# stm.net
KiCad netlist of a schematic drawn in Altium Designer
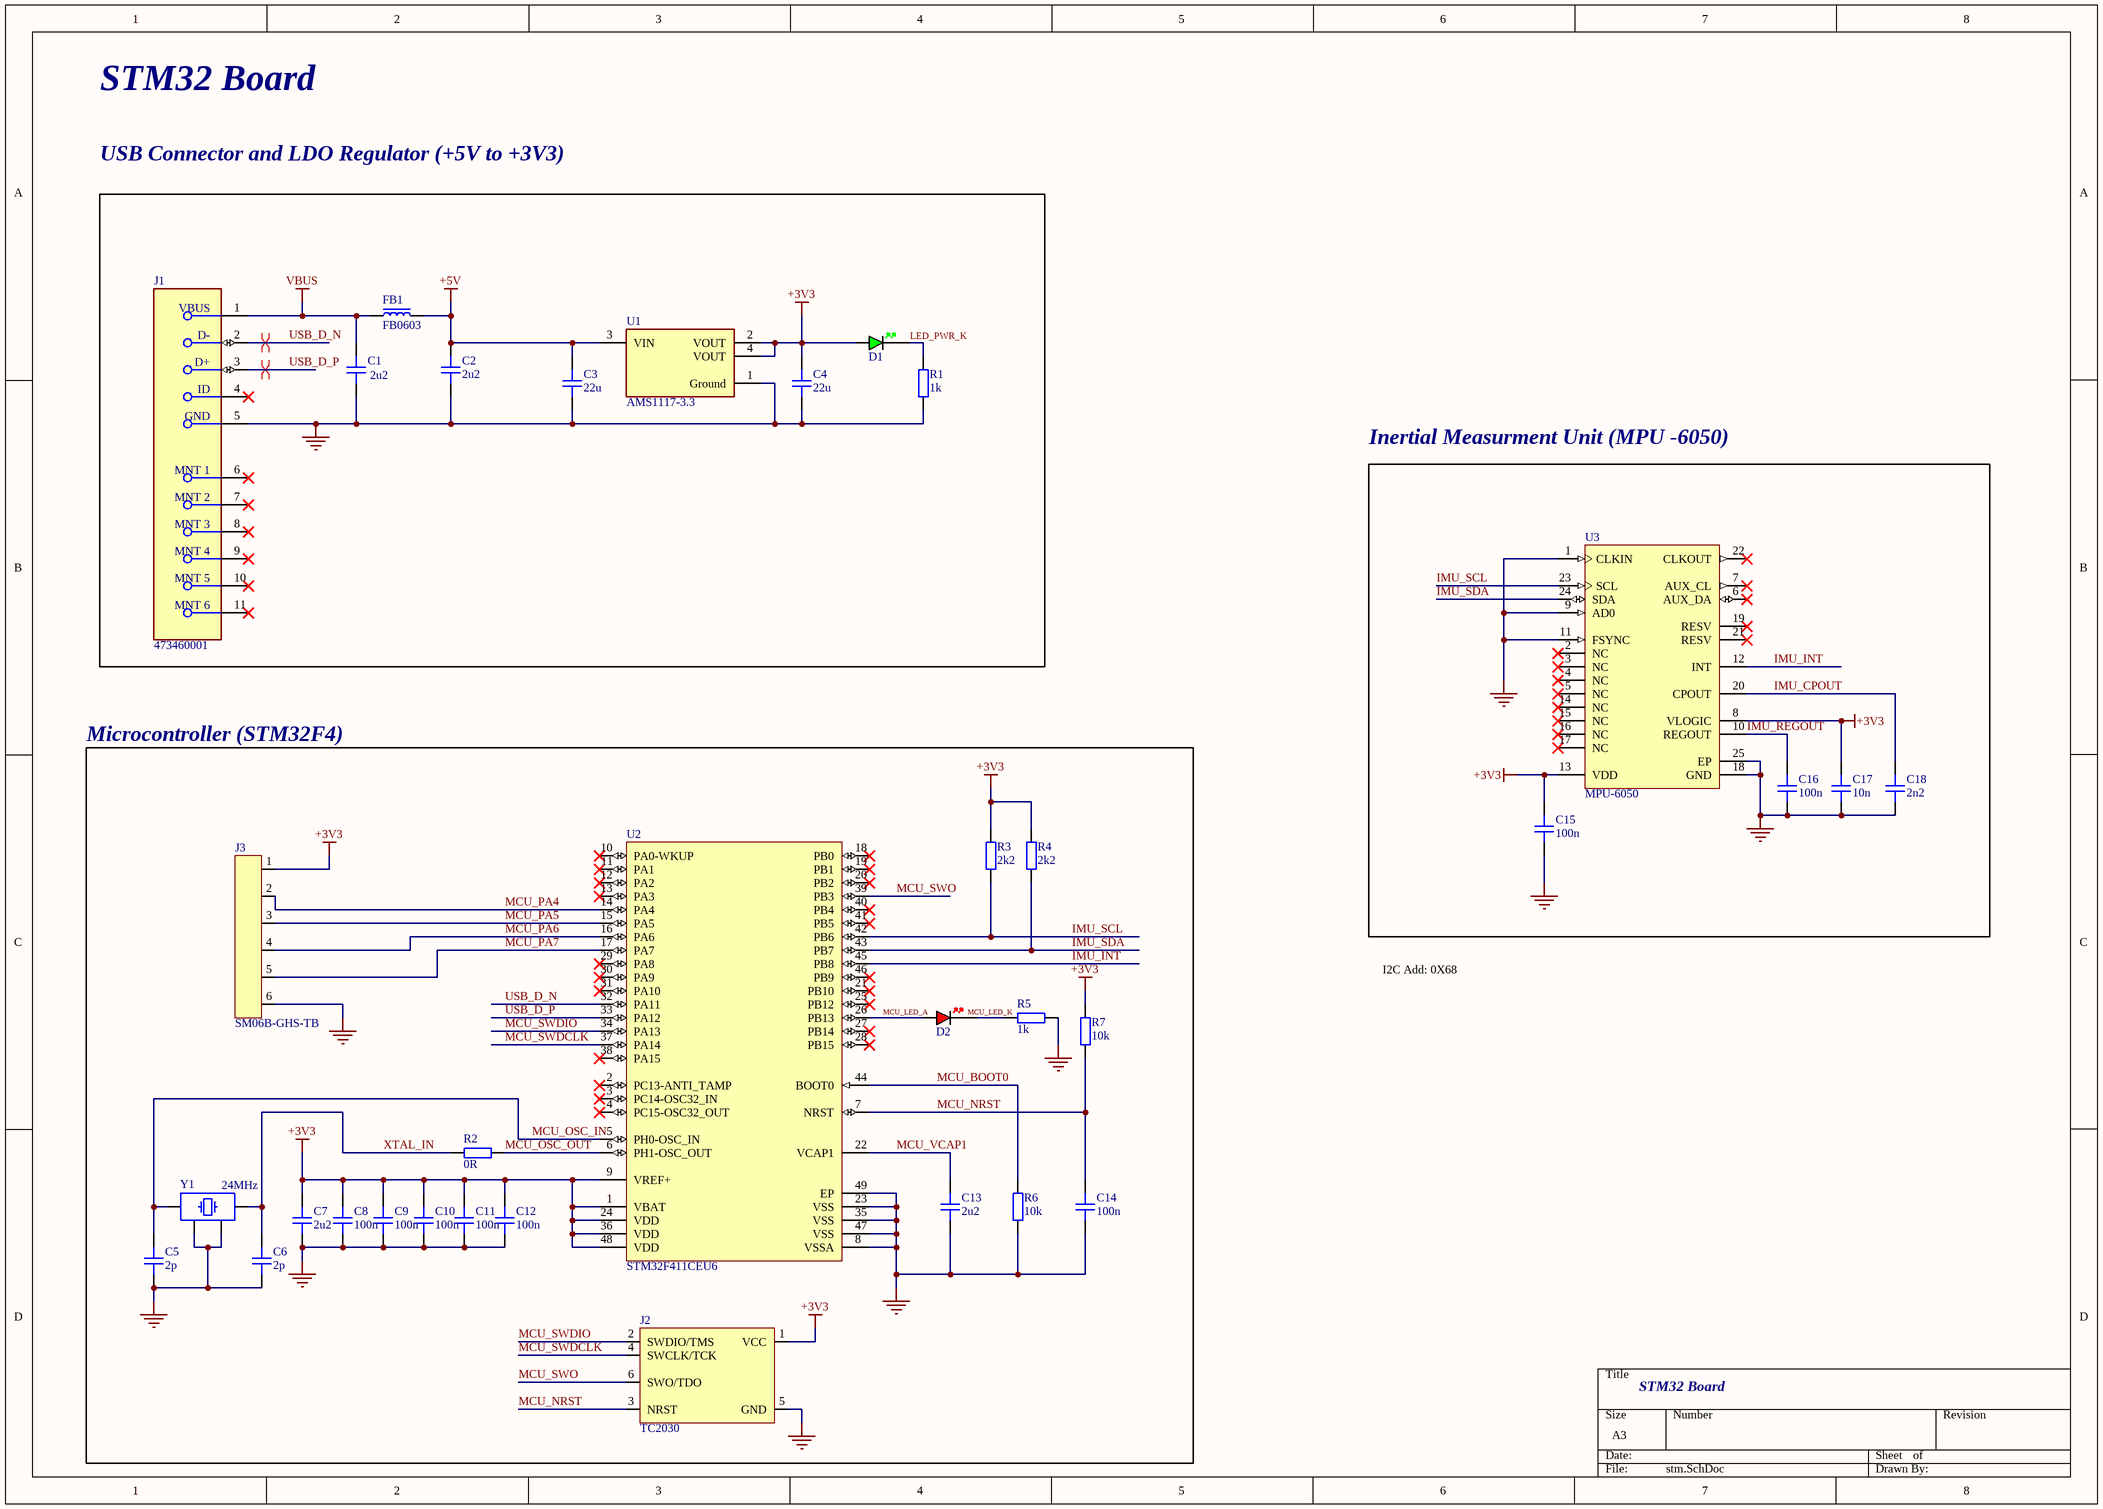
[diagram p0: stm.SchDoc]

(export (version "E")
  (design (tool "Eeschema 10.0.6"))
  (components
    (comp (ref "C1")
      (value "2u2")
      (footprint "CAP_0603")
      (description "Capacitor SMD 0603")
      (libsource (lib "Schematic-Lib-PhilsLab") (part "CAP_0603"))
    )
    (comp (ref "C2")
      (value "2u2")
      (footprint "CAP_0603")
      (description "Capacitor SMD 0603")
      (libsource (lib "Schematic-Lib-PhilsLab") (part "CAP_0603"))
    )
    (comp (ref "C3")
      (value "22u")
      (footprint "CAP_0805")
      (description "Capacitor SMD 0805")
      (libsource (lib "Schematic-Lib-PhilsLab") (part "CAP_0805"))
    )
    (comp (ref "C4")
      (value "22u")
      (footprint "CAP_0805")
      (description "Capacitor SMD 0805")
      (libsource (lib "Schematic-Lib-PhilsLab") (part "CAP_0805"))
    )
    (comp (ref "C5")
      (value "2p")
      (footprint "CAP_0402")
      (description "Capacitor SMD 0402")
      (libsource (lib "Schematic-Lib-PhilsLab") (part "CAP_0402"))
    )
    (comp (ref "C6")
      (value "2p")
      (footprint "CAP_0402")
      (description "Capacitor SMD 0402")
      (libsource (lib "Schematic-Lib-PhilsLab") (part "CAP_0402"))
    )
    (comp (ref "C7")
      (value "2u2")
      (footprint "CAP_0603")
      (description "Capacitor SMD 0603")
      (libsource (lib "Schematic-Lib-PhilsLab") (part "CAP_0603"))
    )
    (comp (ref "C8")
      (value "100n")
      (footprint "CAP_0402")
      (description "Capacitor SMD 0402")
      (libsource (lib "Schematic-Lib-PhilsLab") (part "CAP_0402"))
    )
    (comp (ref "C9")
      (value "100n")
      (footprint "CAP_0402")
      (description "Capacitor SMD 0402")
      (libsource (lib "Schematic-Lib-PhilsLab") (part "CAP_0402"))
    )
    (comp (ref "C10")
      (value "100n")
      (footprint "CAP_0402")
      (description "Capacitor SMD 0402")
      (libsource (lib "Schematic-Lib-PhilsLab") (part "CAP_0402"))
    )
    (comp (ref "C11")
      (value "100n")
      (footprint "CAP_0402")
      (description "Capacitor SMD 0402")
      (libsource (lib "Schematic-Lib-PhilsLab") (part "CAP_0402"))
    )
    (comp (ref "C12")
      (value "100n")
      (footprint "CAP_0402")
      (description "Capacitor SMD 0402")
      (libsource (lib "Schematic-Lib-PhilsLab") (part "CAP_0402"))
    )
    (comp (ref "C13")
      (value "2u2")
      (footprint "CAP_0603")
      (description "Capacitor SMD 0603")
      (libsource (lib "Schematic-Lib-PhilsLab") (part "CAP_0603"))
    )
    (comp (ref "C14")
      (value "100n")
      (footprint "CAP_0402")
      (description "Capacitor SMD 0402")
      (libsource (lib "Schematic-Lib-PhilsLab") (part "CAP_0402"))
    )
    (comp (ref "C15")
      (value "100n")
      (footprint "CAP_0402")
      (description "Capacitor SMD 0402")
      (libsource (lib "Schematic-Lib-PhilsLab") (part "CAP_0402"))
    )
    (comp (ref "C16")
      (value "100n")
      (footprint "CAP_0402")
      (description "Capacitor SMD 0402")
      (libsource (lib "Schematic-Lib-PhilsLab") (part "CAP_0402"))
    )
    (comp (ref "C17")
      (value "10n")
      (footprint "CAP_0402")
      (description "Capacitor SMD 0402")
      (libsource (lib "Schematic-Lib-PhilsLab") (part "CAP_0402"))
    )
    (comp (ref "C18")
      (value "2n2")
      (footprint "CAP_0402")
      (description "Capacitor SMD 0402")
      (libsource (lib "Schematic-Lib-PhilsLab") (part "CAP_0402"))
    )
    (comp (ref "D1")
      (value "GREEN")
      (footprint "LED_0402_GREEN")
      (description "LED 0402 GREEN SMD")
      (libsource (lib "Schematic-Lib-PhilsLab") (part "LED_0402_GREEN"))
    )
    (comp (ref "D2")
      (value "RED")
      (footprint "LED_0402_RED")
      (description "LED 0402 RED SMD")
      (libsource (lib "Schematic-Lib-PhilsLab") (part "LED_0402_RED"))
    )
    (comp (ref "FB1")
      (value "FB0603")
      (footprint "FB_0603")
      (description "Ferrite Bead SMD 0603")
      (libsource (lib "Schematic-Lib-PhilsLab") (part "FB_0603"))
    )
    (comp (ref "J1")
      (value "473460001")
      (footprint "FP-473460001-MFG")
      (description "CONN RCPT USB2.0 MICRO B SMD R/A")
      (fields
        (field (name "OCTOPART") "https://octopart.com/47346-0001-molex-7164928")
        (field (name "MANUFACTURER") "Molex")
      )
      (libsource (lib "Altium Content Vault") (part "53ae1f1d9b557310b43ca686e5bb76a"))
    )
    (comp (ref "J2")
      (value "TC2030")
      (footprint "TC2030-FP")
      (description "Tag-Connect No-Solder SWD Debug Connector DO NOT PLACE")
      (fields (field (name "MANUFACTURER") "Tag-Connect"))
      (libsource (lib "Schematic-Lib-PhilsLab") (part "TC2030"))
    )
    (comp (ref "J3")
      (value "SM06B-GHS-TB")
      (footprint "SM06B-GHS-TB")
      (description "Header Connector 6 Position 1.25MM Pitch SMD Horizontal JST GH")
      (fields (field (name "MANUFACTURER") "JST"))
      (libsource (lib "Schematic-Lib-PhilsLab") (part "SM06B-GHS-TB"))
    )
    (comp (ref "R1")
      (value "1k")
      (footprint "RES_0402")
      (description "Resistor SMD 0402")
      (libsource (lib "Schematic-Lib-PhilsLab") (part "RES_0402"))
    )
    (comp (ref "R2")
      (value "0R")
      (footprint "RES_0402")
      (description "Resistor SMD 0402")
      (libsource (lib "Schematic-Lib-PhilsLab") (part "RES_0402"))
    )
    (comp (ref "R3")
      (value "2k2")
      (footprint "RES_0402")
      (description "Resistor SMD 0402")
      (libsource (lib "Schematic-Lib-PhilsLab") (part "RES_0402"))
    )
    (comp (ref "R4")
      (value "2k2")
      (footprint "RES_0402")
      (description "Resistor SMD 0402")
      (libsource (lib "Schematic-Lib-PhilsLab") (part "RES_0402"))
    )
    (comp (ref "R5")
      (value "1k")
      (footprint "RES_0402")
      (description "Resistor SMD 0402")
      (libsource (lib "Schematic-Lib-PhilsLab") (part "RES_0402"))
    )
    (comp (ref "R6")
      (value "10k")
      (footprint "RES_0402")
      (description "Resistor SMD 0402")
      (libsource (lib "Schematic-Lib-PhilsLab") (part "RES_0402"))
    )
    (comp (ref "R7")
      (value "10k")
      (footprint "RES_0402")
      (description "Resistor SMD 0402")
      (libsource (lib "Schematic-Lib-PhilsLab") (part "RES_0402"))
    )
    (comp (ref "U1")
      (value "AMS1117-3.3")
      (footprint "FP-AMS1117-IPC_C")
      (description "LDO Voltage Regulators 1A, 3.3V")
      (fields
        (field (name "OCTOPART") "https://octopart.com/ams1117-3.3-advanced+monolithic+systems-25899300")
        (field (name "MANUFACTURER") "Advanced Monolithic Systems")
      )
      (libsource (lib "Altium Content Vault") (part "8bdbb5f8e77002000e30dd2845d0354"))
    )
    (comp (ref "U2")
      (value "STM32F411CEU6")
      (footprint "STM-UFQFPN48_L")
      (libsource (lib "Altium Content Vault") (part "MC-ARM-STM32F411-UFQFPN48"))
    )
    (comp (ref "U3")
      (value "MPU-6050")
      (footprint "IS-QFN-24_V")
      (fields (field (name "MANUFACTURER") "InvenSense"))
      (libsource (lib "Altium Content Vault") (part "IS-MPU-6050-QFN-24"))
    )
    (comp (ref "Y1")
      (value "24MHz")
      (footprint "XTAL_3225")
      (description "Crystal SMD 24MHz 10PPM 7pF 3225")
      (fields
        (field (name "MANUFACTURER") "Epson")
        (field (name "MANUFACTURER PART NUMBER") "TSX-3225 24.0000MF15X-AC")
      )
      (libsource (lib "Schematic-Lib-PhilsLab") (part "TSX-3225_24.0000MF15X-AC"))
    )
  )
  (nets
    (net (code "1") (name "+3V3") (class "Default")
      (node (ref "C10") (pin "2") (pinfunction "2_2") (pintype "passive"))
      (node (ref "C11") (pin "2") (pinfunction "2_2") (pintype "passive"))
      (node (ref "C12") (pin "2") (pinfunction "2_2") (pintype "passive"))
      (node (ref "C15") (pin "2") (pinfunction "2_2") (pintype "passive"))
      (node (ref "C17") (pin "2") (pinfunction "2_2") (pintype "passive"))
      (node (ref "C4") (pin "2") (pinfunction "2_2") (pintype "passive"))
      (node (ref "C7") (pin "2") (pinfunction "2_2") (pintype "passive"))
      (node (ref "C8") (pin "2") (pinfunction "2_2") (pintype "passive"))
      (node (ref "C9") (pin "2") (pinfunction "2_2") (pintype "passive"))
      (node (ref "D1") (pin "A") (pinfunction "A_A") (pintype "passive"))
      (node (ref "J2") (pin "1") (pinfunction "VCC_1") (pintype "passive"))
      (node (ref "J3") (pin "1") (pinfunction "1_1") (pintype "passive"))
      (node (ref "R3") (pin "2") (pinfunction "2_2") (pintype "passive"))
      (node (ref "R4") (pin "2") (pinfunction "2_2") (pintype "passive"))
      (node (ref "R7") (pin "2") (pinfunction "2_2") (pintype "passive"))
      (node (ref "U1") (pin "2") (pinfunction "VOUT_2") (pintype "passive"))
      (node (ref "U1") (pin "4") (pinfunction "VOUT_4") (pintype "passive"))
      (node (ref "U2") (pin "1") (pinfunction "VBAT_1") (pintype "power_in"))
      (node (ref "U2") (pin "24") (pinfunction "VDD_24") (pintype "power_in"))
      (node (ref "U2") (pin "36") (pinfunction "VDD_36") (pintype "power_in"))
      (node (ref "U2") (pin "48") (pinfunction "VDD_48") (pintype "power_in"))
      (node (ref "U2") (pin "9") (pinfunction "VREF+_9") (pintype "power_in"))
      (node (ref "U3") (pin "13") (pinfunction "VDD_13") (pintype "power_in"))
      (node (ref "U3") (pin "8") (pinfunction "VLOGIC_8") (pintype "power_in"))
    )
    (net (code "2") (name "+5V") (class "Default")
      (node (ref "C2") (pin "2") (pinfunction "2_2") (pintype "passive"))
      (node (ref "C3") (pin "2") (pinfunction "2_2") (pintype "passive"))
      (node (ref "FB1") (pin "2") (pinfunction "2_2") (pintype "passive"))
      (node (ref "U1") (pin "3") (pinfunction "VIN_3") (pintype "power_in"))
    )
    (net (code "3") (name "/IMU_CPOUT") (class "Default")
      (node (ref "C18") (pin "2") (pinfunction "2_2") (pintype "passive"))
      (node (ref "U3") (pin "20") (pinfunction "CPOUT_20") (pintype "passive"))
    )
    (net (code "4") (name "/IMU_INT") (class "Default")
      (node (ref "U2") (pin "45") (pinfunction "PB8_45") (pintype "bidirectional"))
      (node (ref "U3") (pin "12") (pinfunction "INT_12") (pintype "open_collector"))
    )
    (net (code "5") (name "/IMU_REGOUT") (class "Default")
      (node (ref "C16") (pin "2") (pinfunction "2_2") (pintype "passive"))
      (node (ref "U3") (pin "10") (pinfunction "REGOUT_10") (pintype "passive"))
    )
    (net (code "6") (name "/IMU_SCL") (class "Default")
      (node (ref "R3") (pin "1") (pinfunction "1_1") (pintype "passive"))
      (node (ref "U2") (pin "42") (pinfunction "PB6_42") (pintype "bidirectional"))
      (node (ref "U3") (pin "23") (pinfunction "SCL_23") (pintype "input"))
    )
    (net (code "7") (name "/IMU_SDA") (class "Default")
      (node (ref "R4") (pin "1") (pinfunction "1_1") (pintype "passive"))
      (node (ref "U2") (pin "43") (pinfunction "PB7_43") (pintype "bidirectional"))
      (node (ref "U3") (pin "24") (pinfunction "SDA_24") (pintype "bidirectional"))
    )
    (net (code "8") (name "/LED_PWR_K") (class "Default")
      (node (ref "D1") (pin "K") (pinfunction "K_K") (pintype "passive"))
      (node (ref "R1") (pin "1") (pinfunction "1_1") (pintype "passive"))
    )
    (net (code "9") (name "/MCU_BOOT0") (class "Default")
      (node (ref "R6") (pin "2") (pinfunction "2_2") (pintype "passive"))
      (node (ref "U2") (pin "44") (pinfunction "BOOT0_44") (pintype "input"))
    )
    (net (code "10") (name "/MCU_LED_A") (class "Default")
      (node (ref "D2") (pin "A") (pinfunction "A_A") (pintype "passive"))
      (node (ref "U2") (pin "26") (pinfunction "PB13_26") (pintype "bidirectional"))
    )
    (net (code "11") (name "/MCU_LED_K") (class "Default")
      (node (ref "D2") (pin "K") (pinfunction "K_K") (pintype "passive"))
      (node (ref "R5") (pin "2") (pinfunction "2_2") (pintype "passive"))
    )
    (net (code "12") (name "/MCU_NRST") (class "Default")
      (node (ref "C14") (pin "2") (pinfunction "2_2") (pintype "passive"))
      (node (ref "J2") (pin "3") (pinfunction "NRST_3") (pintype "passive"))
      (node (ref "R7") (pin "1") (pinfunction "1_1") (pintype "passive"))
      (node (ref "U2") (pin "7") (pinfunction "NRST_7") (pintype "bidirectional"))
    )
    (net (code "13") (name "/MCU_OSC_IN") (class "Default")
      (node (ref "C5") (pin "2") (pinfunction "2_2") (pintype "passive"))
      (node (ref "U2") (pin "5") (pinfunction "PH0-OSC_IN_5") (pintype "bidirectional"))
      (node (ref "Y1") (pin "1") (pinfunction "1_1") (pintype "passive"))
    )
    (net (code "14") (name "/MCU_OSC_OUT") (class "Default")
      (node (ref "R2") (pin "1") (pinfunction "1_1") (pintype "passive"))
      (node (ref "U2") (pin "6") (pinfunction "PH1-OSC_OUT_6") (pintype "bidirectional"))
    )
    (net (code "15") (name "/MCU_PA4") (class "Default")
      (node (ref "J3") (pin "2") (pinfunction "2_2") (pintype "passive"))
      (node (ref "U2") (pin "14") (pinfunction "PA4_14") (pintype "bidirectional"))
    )
    (net (code "16") (name "/MCU_PA5") (class "Default")
      (node (ref "J3") (pin "3") (pinfunction "3_3") (pintype "passive"))
      (node (ref "U2") (pin "15") (pinfunction "PA5_15") (pintype "bidirectional"))
    )
    (net (code "17") (name "/MCU_PA6") (class "Default")
      (node (ref "J3") (pin "4") (pinfunction "4_4") (pintype "passive"))
      (node (ref "U2") (pin "16") (pinfunction "PA6_16") (pintype "bidirectional"))
    )
    (net (code "18") (name "/MCU_PA7") (class "Default")
      (node (ref "J3") (pin "5") (pinfunction "5_5") (pintype "passive"))
      (node (ref "U2") (pin "17") (pinfunction "PA7_17") (pintype "bidirectional"))
    )
    (net (code "19") (name "/MCU_SWDCLK") (class "Default")
      (node (ref "J2") (pin "4") (pinfunction "SWCLK/TCK_4") (pintype "passive"))
      (node (ref "U2") (pin "37") (pinfunction "PA14_37") (pintype "bidirectional"))
    )
    (net (code "20") (name "/MCU_SWDIO") (class "Default")
      (node (ref "J2") (pin "2") (pinfunction "SWDIO/TMS_2") (pintype "passive"))
      (node (ref "U2") (pin "34") (pinfunction "PA13_34") (pintype "bidirectional"))
    )
    (net (code "21") (name "/MCU_SWO") (class "Default")
      (node (ref "J2") (pin "6") (pinfunction "SWO/TDO_6") (pintype "passive"))
      (node (ref "U2") (pin "39") (pinfunction "PB3_39") (pintype "bidirectional"))
    )
    (net (code "22") (name "/MCU_VCAP1") (class "Default")
      (node (ref "C13") (pin "2") (pinfunction "2_2") (pintype "passive"))
      (node (ref "U2") (pin "22") (pinfunction "VCAP1_22") (pintype "passive"))
    )
    (net (code "23") (name "/USB_D_N") (class "Default")
      (node (ref "J1") (pin "2") (pinfunction "D-_2") (pintype "bidirectional"))
      (node (ref "U2") (pin "32") (pinfunction "PA11_32") (pintype "bidirectional"))
    )
    (net (code "24") (name "/USB_D_P") (class "Default")
      (node (ref "J1") (pin "3") (pinfunction "D+_3") (pintype "bidirectional"))
      (node (ref "U2") (pin "33") (pinfunction "PA12_33") (pintype "bidirectional"))
    )
    (net (code "25") (name "/XTAL_IN") (class "Default")
      (node (ref "C6") (pin "2") (pinfunction "2_2") (pintype "passive"))
      (node (ref "R2") (pin "2") (pinfunction "2_2") (pintype "passive"))
      (node (ref "Y1") (pin "3") (pinfunction "3_3") (pintype "passive"))
    )
    (net (code "26") (name "GND") (class "Default")
      (node (ref "C1") (pin "1") (pinfunction "1_1") (pintype "passive"))
      (node (ref "C10") (pin "1") (pinfunction "1_1") (pintype "passive"))
      (node (ref "C11") (pin "1") (pinfunction "1_1") (pintype "passive"))
      (node (ref "C12") (pin "1") (pinfunction "1_1") (pintype "passive"))
      (node (ref "C13") (pin "1") (pinfunction "1_1") (pintype "passive"))
      (node (ref "C14") (pin "1") (pinfunction "1_1") (pintype "passive"))
      (node (ref "C15") (pin "1") (pinfunction "1_1") (pintype "passive"))
      (node (ref "C16") (pin "1") (pinfunction "1_1") (pintype "passive"))
      (node (ref "C17") (pin "1") (pinfunction "1_1") (pintype "passive"))
      (node (ref "C18") (pin "1") (pinfunction "1_1") (pintype "passive"))
      (node (ref "C2") (pin "1") (pinfunction "1_1") (pintype "passive"))
      (node (ref "C3") (pin "1") (pinfunction "1_1") (pintype "passive"))
      (node (ref "C4") (pin "1") (pinfunction "1_1") (pintype "passive"))
      (node (ref "C5") (pin "1") (pinfunction "1_1") (pintype "passive"))
      (node (ref "C6") (pin "1") (pinfunction "1_1") (pintype "passive"))
      (node (ref "C7") (pin "1") (pinfunction "1_1") (pintype "passive"))
      (node (ref "C8") (pin "1") (pinfunction "1_1") (pintype "passive"))
      (node (ref "C9") (pin "1") (pinfunction "1_1") (pintype "passive"))
      (node (ref "J1") (pin "5") (pinfunction "GND_5") (pintype "power_in"))
      (node (ref "J2") (pin "5") (pinfunction "GND_5") (pintype "passive"))
      (node (ref "J3") (pin "6") (pinfunction "6_6") (pintype "passive"))
      (node (ref "R1") (pin "2") (pinfunction "2_2") (pintype "passive"))
      (node (ref "R5") (pin "1") (pinfunction "1_1") (pintype "passive"))
      (node (ref "R6") (pin "1") (pinfunction "1_1") (pintype "passive"))
      (node (ref "U1") (pin "1") (pinfunction "Ground_1") (pintype "power_in"))
      (node (ref "U2") (pin "23") (pinfunction "VSS_23") (pintype "power_in"))
      (node (ref "U2") (pin "35") (pinfunction "VSS_35") (pintype "power_in"))
      (node (ref "U2") (pin "47") (pinfunction "VSS_47") (pintype "power_in"))
      (node (ref "U2") (pin "49") (pinfunction "EP_49") (pintype "power_in"))
      (node (ref "U2") (pin "8") (pinfunction "VSSA_8") (pintype "power_in"))
      (node (ref "U3") (pin "1") (pinfunction "CLKIN_1") (pintype "input"))
      (node (ref "U3") (pin "11") (pinfunction "FSYNC_11") (pintype "input"))
      (node (ref "U3") (pin "18") (pinfunction "GND_18") (pintype "power_in"))
      (node (ref "U3") (pin "25") (pinfunction "EP_25") (pintype "power_in"))
      (node (ref "U3") (pin "9") (pinfunction "AD0_9") (pintype "input"))
      (node (ref "Y1") (pin "2") (pinfunction "2_2") (pintype "passive"))
      (node (ref "Y1") (pin "4") (pinfunction "4_4") (pintype "passive"))
    )
    (net (code "27") (name "VBUS") (class "Default")
      (node (ref "C1") (pin "2") (pinfunction "2_2") (pintype "passive"))
      (node (ref "FB1") (pin "1") (pinfunction "1_1") (pintype "passive"))
      (node (ref "J1") (pin "1") (pinfunction "VBUS_1") (pintype "power_in"))
    )
    (net (code "28") (name "unconnected-(J1-ID-Pad4)") (class "Default")
      (node (ref "J1") (pin "4") (pinfunction "ID_4") (pintype "passive+no_connect"))
    )
    (net (code "29") (name "unconnected-(J1-MNT_1-Pad6)") (class "Default")
      (node (ref "J1") (pin "6") (pinfunction "MNT_1_6") (pintype "passive+no_connect"))
    )
    (net (code "30") (name "unconnected-(J1-MNT_2-Pad7)") (class "Default")
      (node (ref "J1") (pin "7") (pinfunction "MNT_2_7") (pintype "passive+no_connect"))
    )
    (net (code "31") (name "unconnected-(J1-MNT_3-Pad8)") (class "Default")
      (node (ref "J1") (pin "8") (pinfunction "MNT_3_8") (pintype "passive+no_connect"))
    )
    (net (code "32") (name "unconnected-(J1-MNT_4-Pad9)") (class "Default")
      (node (ref "J1") (pin "9") (pinfunction "MNT_4_9") (pintype "passive+no_connect"))
    )
    (net (code "33") (name "unconnected-(J1-MNT_5-Pad10)") (class "Default")
      (node (ref "J1") (pin "10") (pinfunction "MNT_5_10") (pintype "passive+no_connect"))
    )
    (net (code "34") (name "unconnected-(J1-MNT_6-Pad11)") (class "Default")
      (node (ref "J1") (pin "11") (pinfunction "MNT_6_11") (pintype "passive+no_connect"))
    )
    (net (code "35") (name "unconnected-(U2-PA0-WKUP-Pad10)") (class "Default")
      (node (ref "U2") (pin "10") (pinfunction "PA0-WKUP_10") (pintype "bidirectional+no_connect"))
    )
    (net (code "36") (name "unconnected-(U2-PA1-Pad11)") (class "Default")
      (node (ref "U2") (pin "11") (pinfunction "PA1_11") (pintype "bidirectional+no_connect"))
    )
    (net (code "37") (name "unconnected-(U2-PA2-Pad12)") (class "Default")
      (node (ref "U2") (pin "12") (pinfunction "PA2_12") (pintype "bidirectional+no_connect"))
    )
    (net (code "38") (name "unconnected-(U2-PA3-Pad13)") (class "Default")
      (node (ref "U2") (pin "13") (pinfunction "PA3_13") (pintype "bidirectional+no_connect"))
    )
    (net (code "39") (name "unconnected-(U2-PA8-Pad29)") (class "Default")
      (node (ref "U2") (pin "29") (pinfunction "PA8_29") (pintype "bidirectional+no_connect"))
    )
    (net (code "40") (name "unconnected-(U2-PA9-Pad30)") (class "Default")
      (node (ref "U2") (pin "30") (pinfunction "PA9_30") (pintype "bidirectional+no_connect"))
    )
    (net (code "41") (name "unconnected-(U2-PA10-Pad31)") (class "Default")
      (node (ref "U2") (pin "31") (pinfunction "PA10_31") (pintype "bidirectional+no_connect"))
    )
    (net (code "42") (name "unconnected-(U2-PA15-Pad38)") (class "Default")
      (node (ref "U2") (pin "38") (pinfunction "PA15_38") (pintype "bidirectional+no_connect"))
    )
    (net (code "43") (name "unconnected-(U2-PB0-Pad18)") (class "Default")
      (node (ref "U2") (pin "18") (pinfunction "PB0_18") (pintype "bidirectional+no_connect"))
    )
    (net (code "44") (name "unconnected-(U2-PB1-Pad19)") (class "Default")
      (node (ref "U2") (pin "19") (pinfunction "PB1_19") (pintype "bidirectional+no_connect"))
    )
    (net (code "45") (name "unconnected-(U2-PB2-Pad20)") (class "Default")
      (node (ref "U2") (pin "20") (pinfunction "PB2_20") (pintype "bidirectional+no_connect"))
    )
    (net (code "46") (name "unconnected-(U2-PB4-Pad40)") (class "Default")
      (node (ref "U2") (pin "40") (pinfunction "PB4_40") (pintype "bidirectional+no_connect"))
    )
    (net (code "47") (name "unconnected-(U2-PB5-Pad41)") (class "Default")
      (node (ref "U2") (pin "41") (pinfunction "PB5_41") (pintype "bidirectional+no_connect"))
    )
    (net (code "48") (name "unconnected-(U2-PB9-Pad46)") (class "Default")
      (node (ref "U2") (pin "46") (pinfunction "PB9_46") (pintype "bidirectional+no_connect"))
    )
    (net (code "49") (name "unconnected-(U2-PB10-Pad21)") (class "Default")
      (node (ref "U2") (pin "21") (pinfunction "PB10_21") (pintype "bidirectional+no_connect"))
    )
    (net (code "50") (name "unconnected-(U2-PB12-Pad25)") (class "Default")
      (node (ref "U2") (pin "25") (pinfunction "PB12_25") (pintype "bidirectional+no_connect"))
    )
    (net (code "51") (name "unconnected-(U2-PB14-Pad27)") (class "Default")
      (node (ref "U2") (pin "27") (pinfunction "PB14_27") (pintype "bidirectional+no_connect"))
    )
    (net (code "52") (name "unconnected-(U2-PB15-Pad28)") (class "Default")
      (node (ref "U2") (pin "28") (pinfunction "PB15_28") (pintype "bidirectional+no_connect"))
    )
    (net (code "53") (name "unconnected-(U2-PC13-ANTI_TAMP-Pad2)") (class "Default")
      (node (ref "U2") (pin "2") (pinfunction "PC13-ANTI_TAMP_2") (pintype "bidirectional+no_connect"))
    )
    (net (code "54") (name "unconnected-(U2-PC14-OSC32_IN-Pad3)") (class "Default")
      (node (ref "U2") (pin "3") (pinfunction "PC14-OSC32_IN_3") (pintype "bidirectional+no_connect"))
    )
    (net (code "55") (name "unconnected-(U2-PC15-OSC32_OUT-Pad4)") (class "Default")
      (node (ref "U2") (pin "4") (pinfunction "PC15-OSC32_OUT_4") (pintype "bidirectional+no_connect"))
    )
    (net (code "56") (name "unconnected-(U3-AUX_CL-Pad7)") (class "Default")
      (node (ref "U3") (pin "7") (pinfunction "AUX_CL_7") (pintype "output+no_connect"))
    )
    (net (code "57") (name "unconnected-(U3-AUX_DA-Pad6)") (class "Default")
      (node (ref "U3") (pin "6") (pinfunction "AUX_DA_6") (pintype "bidirectional+no_connect"))
    )
    (net (code "58") (name "unconnected-(U3-CLKOUT-Pad22)") (class "Default")
      (node (ref "U3") (pin "22") (pinfunction "CLKOUT_22") (pintype "output+no_connect"))
    )
    (net (code "59") (name "unconnected-(U3-NC-Pad2)") (class "Default")
      (node (ref "U3") (pin "2") (pinfunction "NC_2") (pintype "passive+no_connect"))
    )
    (net (code "60") (name "unconnected-(U3-NC-Pad3)") (class "Default")
      (node (ref "U3") (pin "3") (pinfunction "NC_3") (pintype "passive+no_connect"))
    )
    (net (code "61") (name "unconnected-(U3-NC-Pad4)") (class "Default")
      (node (ref "U3") (pin "4") (pinfunction "NC_4") (pintype "passive+no_connect"))
    )
    (net (code "62") (name "unconnected-(U3-NC-Pad5)") (class "Default")
      (node (ref "U3") (pin "5") (pinfunction "NC_5") (pintype "passive+no_connect"))
    )
    (net (code "63") (name "unconnected-(U3-NC-Pad14)") (class "Default")
      (node (ref "U3") (pin "14") (pinfunction "NC_14") (pintype "passive+no_connect"))
    )
    (net (code "64") (name "unconnected-(U3-NC-Pad15)") (class "Default")
      (node (ref "U3") (pin "15") (pinfunction "NC_15") (pintype "passive+no_connect"))
    )
    (net (code "65") (name "unconnected-(U3-NC-Pad16)") (class "Default")
      (node (ref "U3") (pin "16") (pinfunction "NC_16") (pintype "passive+no_connect"))
    )
    (net (code "66") (name "unconnected-(U3-NC-Pad17)") (class "Default")
      (node (ref "U3") (pin "17") (pinfunction "NC_17") (pintype "passive+no_connect"))
    )
    (net (code "67") (name "unconnected-(U3-RESV-Pad19)") (class "Default")
      (node (ref "U3") (pin "19") (pinfunction "RESV_19") (pintype "passive+no_connect"))
    )
    (net (code "68") (name "unconnected-(U3-RESV-Pad21)") (class "Default")
      (node (ref "U3") (pin "21") (pinfunction "RESV_21") (pintype "passive+no_connect"))
    )
  )
)
